# iTimeAfrica_v1_1.net
KiCad netlist of a schematic drawn in Altium Designer
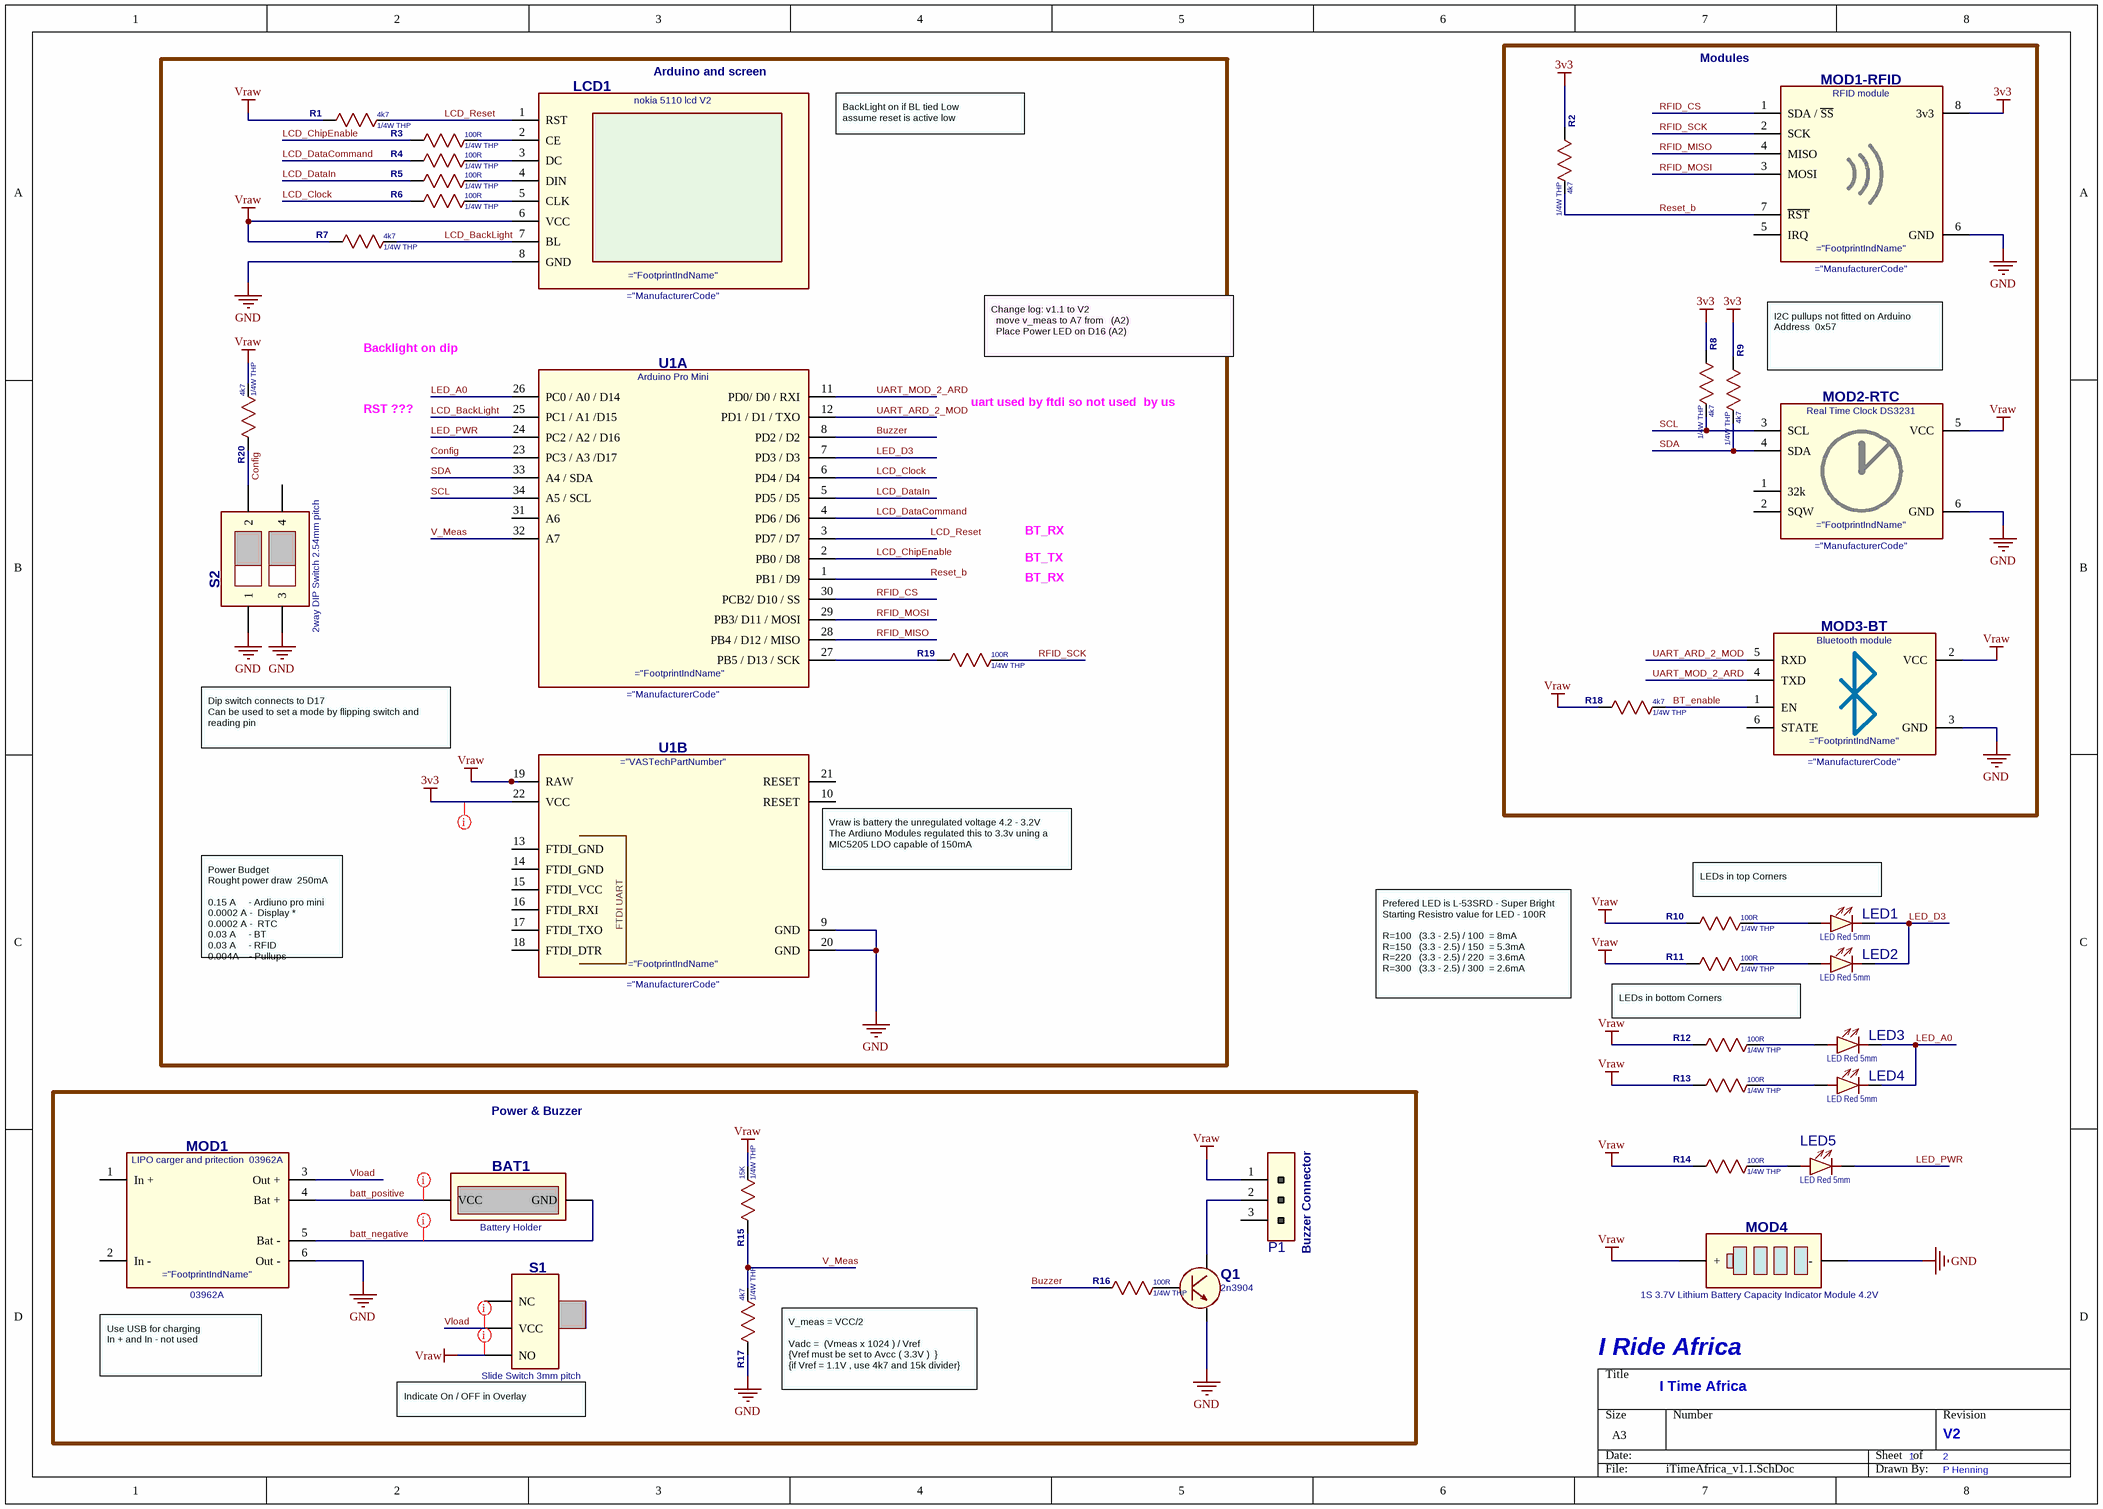
[diagram p0: iTimeAfrica_v1.1.SchDoc]

(export (version "E")
  (design (tool "Eeschema 10.0.6"))
  (components
    (comp (ref "BAT1")
      (value "Battery Holder")
      (footprint "Battery Holder")
      (libsource (lib "Copy of Undero_Symbols_v7") (part "Battery Holder"))
    )
    (comp (ref "LCD1")
      (value "nokia 5110 lcd")
      (footprint "Nokia 5110 GLCD 84x48")
      (description "nokia 5110 lcd V2")
      (fields (field (name "MANUFACTURER") "unknown"))
      (libsource (lib "Copy of Undero_Symbols_v7") (part "nokia 5110 lcd V2"))
    )
    (comp (ref "LED1")
      (value "LED Red 5mm")
      (footprint "LED THL 5x9mm Vert")
      (description "Red LED, 5mm THP")
      (fields
        (field (name "MANUFACTURERPARTNUMBER") "L-53SR")
        (field (name "MANUFACTURER") "kingbright")
        (field (name "ATTRIBUTES") "LED Red 5mm")
      )
      (libsource (lib "Copy of Undero_Symbols_v7") (part "Red LED THP"))
    )
    (comp (ref "LED2")
      (value "LED Red 5mm")
      (footprint "LED THL 5x9mm Vert")
      (description "Red LED, 5mm THP")
      (fields
        (field (name "MANUFACTURERPARTNUMBER") "L-53SR")
        (field (name "MANUFACTURER") "kingbright")
        (field (name "ATTRIBUTES") "LED Red 5mm")
      )
      (libsource (lib "Copy of Undero_Symbols_v7") (part "Red LED THP"))
    )
    (comp (ref "LED3")
      (value "LED Red 5mm")
      (footprint "LED THL 5x9mm Vert")
      (description "Red LED, 5mm THP")
      (fields
        (field (name "MANUFACTURERPARTNUMBER") "L-53SR")
        (field (name "MANUFACTURER") "kingbright")
        (field (name "ATTRIBUTES") "LED Red 5mm")
      )
      (libsource (lib "Copy of Undero_Symbols_v7") (part "Red LED THP"))
    )
    (comp (ref "LED4")
      (value "LED Red 5mm")
      (footprint "LED THL 5x9mm Vert")
      (description "Red LED, 5mm THP")
      (fields
        (field (name "MANUFACTURERPARTNUMBER") "L-53SR")
        (field (name "MANUFACTURER") "kingbright")
        (field (name "ATTRIBUTES") "LED Red 5mm")
      )
      (libsource (lib "Copy of Undero_Symbols_v7") (part "Red LED THP"))
    )
    (comp (ref "LED5")
      (value "LED Red 5mm")
      (footprint "LED THL 5x9mm Vert")
      (description "Red LED, 5mm THP")
      (fields
        (field (name "MANUFACTURERPARTNUMBER") "L-53SR")
        (field (name "MANUFACTURER") "kingbright")
        (field (name "ATTRIBUTES") "LED Red 5mm")
      )
      (libsource (lib "Copy of Undero_Symbols_v7") (part "Red LED THP"))
    )
    (comp (ref "MOD1")
      (value "Real Time Clock DS3231")
      (footprint "Charger/protection")
      (description "LIPO carger and pritection  03962A")
      (fields (field (name "MANUFACTURERPARTNUMBER") "03962A"))
      (libsource (lib "iTimeAfrica_Symbol") (part "Charger / Protection"))
    )
    (comp (ref "MOD1-RFID")
      (value "RFID module")
      (footprint "RFID-RC522")
      (fields (field (name "MANUFACTURERPARTNUMBER") "RFID-RC533"))
      (libsource (lib "Copy of Undero_Symbols_v7") (part "RFID module"))
    )
    (comp (ref "MOD2-RTC")
      (value "Real Time Clock DS3231")
      (footprint "RTC DS3231")
      (libsource (lib "Copy of Undero_Symbols_v7") (part "Real Time Clock DS3231"))
    )
    (comp (ref "MOD3-BT")
      (value "Bluetooth module")
      (footprint "BlueTooth Card")
      (libsource (lib "Copy of Undero_Symbols_v7") (part "Bluetooth module"))
    )
    (comp (ref "MOD4")
      (value "1S 3.7V Lithium Battery Capacity Indicator Module 4.2V")
      (footprint "Battery Indicator")
      (libsource (lib "Copy of Undero_Symbols_v7") (part "Battery Indicator"))
    )
    (comp (ref "P1")
      (value "3 pin Screw Terminal 3.5mm")
      (footprint "3x1 Screw terminal 3.5mm")
      (fields (field (name "MANUFACTURERPARTNUMBER") "1984950") (field (name "MANUFACTURER") "RS"))
      (libsource (lib "Copy of Undero_Symbols_v7") (part "3 pin Screw Terminal 3.5mm"))
    )
    (comp (ref "Q1")
      (value "2n3904")
      (footprint "TO-92")
      (description "NPN Transistor")
      (fields (field (name "MANUFACTURER") "Fairchild") (field (name "ATTRIBUTES") "2n3904"))
      (libsource (lib "Copy of Undero_Symbols_v7") (part "NPN Transistor"))
    )
    (comp (ref "R1")
      (value "4k7")
      (footprint "Res 1/4W THP")
      (description "Resistor")
      (fields (field (name "PACKAGE") "1/4W THP") (field (name "ATTRIBUTES") "4k7"))
      (libsource (lib "Copy of Undero_Symbols_v7") (part "4k7"))
    )
    (comp (ref "R2")
      (value "4k7")
      (footprint "Res 1/4W THP")
      (description "Resistor")
      (fields (field (name "PACKAGE") "1/4W THP") (field (name "ATTRIBUTES") "4k7"))
      (libsource (lib "Copy of Undero_Symbols_v7") (part "4k7"))
    )
    (comp (ref "R3")
      (value "100R")
      (footprint "Res 1/4W THP")
      (description "Resistor")
      (fields (field (name "PACKAGE") "1/4W THP") (field (name "ATTRIBUTES") "100R"))
      (libsource (lib "Copy of Undero_Symbols_v7") (part "100R"))
    )
    (comp (ref "R4")
      (value "100R")
      (footprint "Res 1/4W THP")
      (description "Resistor")
      (fields (field (name "PACKAGE") "1/4W THP") (field (name "ATTRIBUTES") "100R"))
      (libsource (lib "Copy of Undero_Symbols_v7") (part "100R"))
    )
    (comp (ref "R5")
      (value "100R")
      (footprint "Res 1/4W THP")
      (description "Resistor")
      (fields (field (name "PACKAGE") "1/4W THP") (field (name "ATTRIBUTES") "100R"))
      (libsource (lib "Copy of Undero_Symbols_v7") (part "100R"))
    )
    (comp (ref "R6")
      (value "100R")
      (footprint "Res 1/4W THP")
      (description "Resistor")
      (fields (field (name "PACKAGE") "1/4W THP") (field (name "ATTRIBUTES") "100R"))
      (libsource (lib "Copy of Undero_Symbols_v7") (part "100R"))
    )
    (comp (ref "R7")
      (value "4k7")
      (footprint "Res 1/4W THP")
      (description "Resistor")
      (fields (field (name "PACKAGE") "1/4W THP") (field (name "ATTRIBUTES") "4k7"))
      (libsource (lib "Copy of Undero_Symbols_v7") (part "4k7"))
    )
    (comp (ref "R8")
      (value "4k7")
      (footprint "Res 1/4W THP")
      (description "Resistor")
      (fields (field (name "PACKAGE") "1/4W THP") (field (name "ATTRIBUTES") "4k7"))
      (libsource (lib "Copy of Undero_Symbols_v7") (part "4k7"))
    )
    (comp (ref "R9")
      (value "4k7")
      (footprint "Res 1/4W THP")
      (description "Resistor")
      (fields (field (name "PACKAGE") "1/4W THP") (field (name "ATTRIBUTES") "4k7"))
      (libsource (lib "Copy of Undero_Symbols_v7") (part "4k7"))
    )
    (comp (ref "R10")
      (value "100R")
      (footprint "Res 1/4W THP")
      (description "Resistor")
      (fields (field (name "PACKAGE") "1/4W THP") (field (name "ATTRIBUTES") "100R"))
      (libsource (lib "Copy of Undero_Symbols_v7") (part "100R"))
    )
    (comp (ref "R11")
      (value "100R")
      (footprint "Res 1/4W THP")
      (description "Resistor")
      (fields (field (name "PACKAGE") "1/4W THP") (field (name "ATTRIBUTES") "100R"))
      (libsource (lib "Copy of Undero_Symbols_v7") (part "100R"))
    )
    (comp (ref "R12")
      (value "100R")
      (footprint "Res 1/4W THP")
      (description "Resistor")
      (fields (field (name "PACKAGE") "1/4W THP") (field (name "ATTRIBUTES") "100R"))
      (libsource (lib "Copy of Undero_Symbols_v7") (part "100R"))
    )
    (comp (ref "R13")
      (value "100R")
      (footprint "Res 1/4W THP")
      (description "Resistor")
      (fields (field (name "PACKAGE") "1/4W THP") (field (name "ATTRIBUTES") "100R"))
      (libsource (lib "Copy of Undero_Symbols_v7") (part "100R"))
    )
    (comp (ref "R14")
      (value "100R")
      (footprint "Res 1/4W THP")
      (description "Resistor")
      (fields (field (name "PACKAGE") "1/4W THP") (field (name "ATTRIBUTES") "100R"))
      (libsource (lib "Copy of Undero_Symbols_v7") (part "100R"))
    )
    (comp (ref "R15")
      (value "15K")
      (footprint "Res 1/4W THP")
      (description "Resistor")
      (fields (field (name "PACKAGE") "1/4W THP") (field (name "ATTRIBUTES") "15K"))
      (libsource (lib "Copy of Undero_Symbols_v7") (part "15K"))
    )
    (comp (ref "R16")
      (value "100R")
      (footprint "Res 1/4W THP")
      (description "Resistor")
      (fields (field (name "PACKAGE") "1/4W THP") (field (name "ATTRIBUTES") "100R"))
      (libsource (lib "Copy of Undero_Symbols_v7") (part "100R"))
    )
    (comp (ref "R17")
      (value "4k7")
      (footprint "Res 1/4W THP")
      (description "Resistor")
      (fields (field (name "PACKAGE") "1/4W THP") (field (name "ATTRIBUTES") "4k7"))
      (libsource (lib "Copy of Undero_Symbols_v7") (part "4k7"))
    )
    (comp (ref "R18")
      (value "4k7")
      (footprint "Res 1/4W THP")
      (description "Resistor")
      (fields (field (name "PACKAGE") "1/4W THP") (field (name "ATTRIBUTES") "4k7"))
      (libsource (lib "Copy of Undero_Symbols_v7") (part "4k7"))
    )
    (comp (ref "R19")
      (value "100R")
      (footprint "Res 1/4W THP")
      (description "Resistor")
      (fields (field (name "PACKAGE") "1/4W THP") (field (name "ATTRIBUTES") "100R"))
      (libsource (lib "Copy of Undero_Symbols_v7") (part "100R"))
    )
    (comp (ref "R20")
      (value "4k7")
      (footprint "Res 1/4W THP")
      (description "Resistor")
      (fields (field (name "PACKAGE") "1/4W THP") (field (name "ATTRIBUTES") "4k7"))
      (libsource (lib "Copy of Undero_Symbols_v7") (part "4k7"))
    )
    (comp (ref "S1")
      (value "Slide Switch 3mm pitch")
      (footprint "Slide Switch 3mm")
      (fields (field (name "MANUFACTURER") "Arcolectric Corporation"))
      (libsource (lib "Copy of Undero_Symbols_v7") (part "Slide Switch 3mm pitch"))
    )
    (comp (ref "S2")
      (value "2x DIP Switch 2.54mm pitch")
      (footprint "2way DIP switch")
      (description "2way DIP Switch 2.54mm pitch")
      (fields
        (field (name "MANUFACTURER") "Arcolectric Corporation")
        (field (name "MANUFACTURERPARTNUMBER") "KTS02E")
      )
      (libsource (lib "Copy of Undero_Symbols_v7") (part "2way DIP Switch 2.54mm pitch"))
    )
    (comp (ref "U1")
      (value "Arduino Pro Mini")
      (footprint "ARDUINO PRO MINI v2 (NO FTDI)")
      (fields
        (field (name "MANUFACTURER") "SparkFun Electronics")
        (field (name "MANUFACTURERPARTNUMBER") "DEV-11113  (check this)")
      )
      (libsource (lib "Copy of Undero_Symbols_v7") (part "Arduino Pro Mini"))
    )
  )
  (nets
    (net (code "1") (name "/BT_enable") (class "Default")
      (node (ref "MOD3-BT") (pin "1") (pinfunction "EN_1") (pintype "passive"))
      (node (ref "R18") (pin "2") (pinfunction "2_2") (pintype "passive"))
    )
    (net (code "2") (name "/Buzzer") (class "Default")
      (node (ref "R16") (pin "1") (pinfunction "1_1") (pintype "passive"))
      (node (ref "U1") (pin "8") (pinfunction "PD2_/_D2_8") (pintype "passive"))
    )
    (net (code "3") (name "/Config") (class "Default")
      (node (ref "R20") (pin "1") (pinfunction "1_1") (pintype "passive"))
      (node (ref "S2") (pin "2") (pinfunction "2_2") (pintype "passive"))
      (node (ref "U1") (pin "23") (pinfunction "PC3_/_A3_/D17_23") (pintype "passive"))
    )
    (net (code "4") (name "/LCD_BackLight") (class "Default")
      (node (ref "LCD1") (pin "7") (pinfunction "BL_7") (pintype "passive"))
      (node (ref "R7") (pin "2") (pinfunction "2_2") (pintype "passive"))
      (node (ref "U1") (pin "25") (pinfunction "PC1_/_A1_/D15_25") (pintype "passive"))
    )
    (net (code "5") (name "/LCD_ChipEnable") (class "Default")
      (node (ref "R3") (pin "1") (pinfunction "1_1") (pintype "passive"))
      (node (ref "U1") (pin "2") (pinfunction "PB0_/_D8_2") (pintype "passive"))
    )
    (net (code "6") (name "/LCD_Clock") (class "Default")
      (node (ref "R6") (pin "1") (pinfunction "1_1") (pintype "passive"))
      (node (ref "U1") (pin "6") (pinfunction "PD4_/_D4_6") (pintype "passive"))
    )
    (net (code "7") (name "/LCD_DataCommand") (class "Default")
      (node (ref "R4") (pin "1") (pinfunction "1_1") (pintype "passive"))
      (node (ref "U1") (pin "4") (pinfunction "PD6_/_D6_4") (pintype "passive"))
    )
    (net (code "8") (name "/LCD_DataIn") (class "Default")
      (node (ref "R5") (pin "1") (pinfunction "1_1") (pintype "passive"))
      (node (ref "U1") (pin "5") (pinfunction "PD5_/_D5_5") (pintype "passive"))
    )
    (net (code "9") (name "/LCD_Reset") (class "Default")
      (node (ref "LCD1") (pin "1") (pinfunction "RST_1") (pintype "passive"))
      (node (ref "R1") (pin "2") (pinfunction "2_2") (pintype "passive"))
      (node (ref "U1") (pin "3") (pinfunction "PD7_/_D7_3") (pintype "passive"))
    )
    (net (code "10") (name "/LED_A0") (class "Default")
      (node (ref "LED3") (pin "2") (pinfunction "C_2") (pintype "passive"))
      (node (ref "LED4") (pin "2") (pinfunction "C_2") (pintype "passive"))
      (node (ref "U1") (pin "26") (pinfunction "PC0_/_A0_/_D14_26") (pintype "passive"))
    )
    (net (code "11") (name "/LED_D3") (class "Default")
      (node (ref "LED1") (pin "2") (pinfunction "C_2") (pintype "passive"))
      (node (ref "LED2") (pin "2") (pinfunction "C_2") (pintype "passive"))
      (node (ref "U1") (pin "7") (pinfunction "PD3_/_D3_7") (pintype "passive"))
    )
    (net (code "12") (name "/LED_PWR") (class "Default")
      (node (ref "LED5") (pin "2") (pinfunction "C_2") (pintype "passive"))
      (node (ref "U1") (pin "24") (pinfunction "PC2_/_A2_/_D16_24") (pintype "passive"))
    )
    (net (code "13") (name "/RFID_CS") (class "Default")
      (node (ref "MOD1-RFID") (pin "1") (pinfunction "SDA_/_~{SS}_1") (pintype "passive"))
      (node (ref "U1") (pin "30") (pinfunction "PCB2/_D10_/_SS_30") (pintype "passive"))
    )
    (net (code "14") (name "/RFID_MISO") (class "Default")
      (node (ref "MOD1-RFID") (pin "4") (pinfunction "MISO_4") (pintype "passive"))
      (node (ref "U1") (pin "28") (pinfunction "PB4_/_D12_/_MISO_28") (pintype "passive"))
    )
    (net (code "15") (name "/RFID_MOSI") (class "Default")
      (node (ref "MOD1-RFID") (pin "3") (pinfunction "MOSI_3") (pintype "passive"))
      (node (ref "U1") (pin "29") (pinfunction "PB3/_D11_/_MOSI_29") (pintype "passive"))
    )
    (net (code "16") (name "/RFID_SCK") (class "Default")
      (node (ref "MOD1-RFID") (pin "2") (pinfunction "SCK_2") (pintype "passive"))
      (node (ref "R19") (pin "2") (pinfunction "2_2") (pintype "passive"))
    )
    (net (code "17") (name "/Reset_b") (class "Default")
      (node (ref "MOD1-RFID") (pin "7") (pinfunction "RST_7") (pintype "passive"))
      (node (ref "R2") (pin "2") (pinfunction "2_2") (pintype "passive"))
      (node (ref "U1") (pin "1") (pinfunction "PB1_/_D9_1") (pintype "passive"))
    )
    (net (code "18") (name "/SCL") (class "Default")
      (node (ref "MOD2-RTC") (pin "3") (pinfunction "SCL_3") (pintype "passive"))
      (node (ref "R8") (pin "2") (pinfunction "2_2") (pintype "passive"))
      (node (ref "U1") (pin "34") (pinfunction "A5_/_SCL_34") (pintype "passive"))
    )
    (net (code "19") (name "/SDA") (class "Default")
      (node (ref "MOD2-RTC") (pin "4") (pinfunction "SDA_4") (pintype "passive"))
      (node (ref "R9") (pin "2") (pinfunction "2_2") (pintype "passive"))
      (node (ref "U1") (pin "33") (pinfunction "A4_/_SDA_33") (pintype "passive"))
    )
    (net (code "20") (name "/UART_ARD_2_MOD") (class "Default")
      (node (ref "MOD3-BT") (pin "5") (pinfunction "RXD_5") (pintype "passive"))
      (node (ref "U1") (pin "12") (pinfunction "PD1_/_D1_/_TXO_12") (pintype "passive"))
    )
    (net (code "21") (name "/UART_MOD_2_ARD") (class "Default")
      (node (ref "MOD3-BT") (pin "4") (pinfunction "TXD_4") (pintype "passive"))
      (node (ref "U1") (pin "11") (pinfunction "PD0/_D0_/_RXI_11") (pintype "passive"))
    )
    (net (code "22") (name "/V_Meas") (class "Default")
      (node (ref "R15") (pin "1") (pinfunction "1_1") (pintype "passive"))
      (node (ref "R17") (pin "2") (pinfunction "2_2") (pintype "passive"))
      (node (ref "U1") (pin "32") (pinfunction "A7_32") (pintype "passive"))
    )
    (net (code "23") (name "/Vload") (class "Default")
      (node (ref "MOD1") (pin "3") (pinfunction "Out_+_3") (pintype "passive"))
      (node (ref "S1") (pin "2") (pinfunction "VCC_2") (pintype "passive"))
    )
    (net (code "24") (name "/batt_negative") (class "Default")
      (node (ref "BAT1") (pin "2") (pinfunction "GND_2") (pintype "passive"))
      (node (ref "MOD1") (pin "5") (pinfunction "Bat_-_5") (pintype "passive"))
    )
    (net (code "25") (name "/batt_positive") (class "Default")
      (node (ref "BAT1") (pin "1") (pinfunction "VCC_1") (pintype "passive"))
      (node (ref "MOD1") (pin "4") (pinfunction "Bat_+_4") (pintype "passive"))
    )
    (net (code "26") (name "3v3") (class "Default")
      (node (ref "MOD1-RFID") (pin "8") (pinfunction "3v3_8") (pintype "passive"))
      (node (ref "R2") (pin "1") (pinfunction "1_1") (pintype "passive"))
      (node (ref "R8") (pin "1") (pinfunction "1_1") (pintype "passive"))
      (node (ref "R9") (pin "1") (pinfunction "1_1") (pintype "passive"))
      (node (ref "U1") (pin "22") (pinfunction "VCC_22") (pintype "passive"))
    )
    (net (code "27") (name "GND") (class "Default")
      (node (ref "LCD1") (pin "8") (pinfunction "GND_8") (pintype "passive"))
      (node (ref "MOD1") (pin "6") (pinfunction "Out_-_6") (pintype "passive"))
      (node (ref "MOD1-RFID") (pin "6") (pinfunction "GND_6") (pintype "passive"))
      (node (ref "MOD2-RTC") (pin "6") (pinfunction "GND_6") (pintype "passive"))
      (node (ref "MOD3-BT") (pin "3") (pinfunction "GND_3") (pintype "passive"))
      (node (ref "MOD4") (pin "2") (pinfunction "-_2") (pintype "passive"))
      (node (ref "Q1") (pin "3") (pinfunction "E_3") (pintype "passive"))
      (node (ref "R17") (pin "1") (pinfunction "1_1") (pintype "passive"))
      (node (ref "S2") (pin "1") (pinfunction "1_1") (pintype "passive"))
      (node (ref "S2") (pin "3") (pinfunction "3_3") (pintype "passive"))
      (node (ref "U1") (pin "20") (pinfunction "GND_20") (pintype "passive"))
      (node (ref "U1") (pin "9") (pinfunction "GND_9") (pintype "passive"))
    )
    (net (code "28") (name "Net-(LCD1-CE)") (class "Default")
      (node (ref "LCD1") (pin "2") (pinfunction "CE_2") (pintype "passive"))
      (node (ref "R3") (pin "2") (pinfunction "2_2") (pintype "passive"))
    )
    (net (code "29") (name "Net-(LCD1-CLK)") (class "Default")
      (node (ref "LCD1") (pin "5") (pinfunction "CLK_5") (pintype "passive"))
      (node (ref "R6") (pin "2") (pinfunction "2_2") (pintype "passive"))
    )
    (net (code "30") (name "Net-(LCD1-DC)") (class "Default")
      (node (ref "LCD1") (pin "3") (pinfunction "DC_3") (pintype "passive"))
      (node (ref "R4") (pin "2") (pinfunction "2_2") (pintype "passive"))
    )
    (net (code "31") (name "Net-(LCD1-DIN)") (class "Default")
      (node (ref "LCD1") (pin "4") (pinfunction "DIN_4") (pintype "passive"))
      (node (ref "R5") (pin "2") (pinfunction "2_2") (pintype "passive"))
    )
    (net (code "32") (name "Net-(LED1-A)") (class "Default")
      (node (ref "LED1") (pin "1") (pinfunction "A_1") (pintype "passive"))
      (node (ref "R10") (pin "2") (pinfunction "2_2") (pintype "passive"))
    )
    (net (code "33") (name "Net-(LED2-A)") (class "Default")
      (node (ref "LED2") (pin "1") (pinfunction "A_1") (pintype "passive"))
      (node (ref "R11") (pin "2") (pinfunction "2_2") (pintype "passive"))
    )
    (net (code "34") (name "Net-(LED3-A)") (class "Default")
      (node (ref "LED3") (pin "1") (pinfunction "A_1") (pintype "passive"))
      (node (ref "R12") (pin "2") (pinfunction "2_2") (pintype "passive"))
    )
    (net (code "35") (name "Net-(LED4-A)") (class "Default")
      (node (ref "LED4") (pin "1") (pinfunction "A_1") (pintype "passive"))
      (node (ref "R13") (pin "2") (pinfunction "2_2") (pintype "passive"))
    )
    (net (code "36") (name "Net-(LED5-A)") (class "Default")
      (node (ref "LED5") (pin "1") (pinfunction "A_1") (pintype "passive"))
      (node (ref "R14") (pin "2") (pinfunction "2_2") (pintype "passive"))
    )
    (net (code "37") (name "Net-(Q1-B)") (class "Default")
      (node (ref "Q1") (pin "2") (pinfunction "B_2") (pintype "passive"))
      (node (ref "R16") (pin "2") (pinfunction "2_2") (pintype "passive"))
    )
    (net (code "38") (name "Net-(Q1-C)") (class "Default")
      (node (ref "P1") (pin "2") (pinfunction "2_2") (pintype "passive"))
      (node (ref "Q1") (pin "1") (pinfunction "C_1") (pintype "passive"))
    )
    (net (code "39") (name "Net-(U1A-PB5_{slash}_D13_{slash}_SCK)") (class "Default")
      (node (ref "R19") (pin "1") (pinfunction "1_1") (pintype "passive"))
      (node (ref "U1") (pin "27") (pinfunction "PB5_/_D13_/_SCK_27") (pintype "passive"))
    )
    (net (code "40") (name "Vraw") (class "Default")
      (node (ref "LCD1") (pin "6") (pinfunction "VCC_6") (pintype "passive"))
      (node (ref "MOD2-RTC") (pin "5") (pinfunction "VCC_5") (pintype "passive"))
      (node (ref "MOD3-BT") (pin "2") (pinfunction "VCC_2") (pintype "passive"))
      (node (ref "MOD4") (pin "1") (pinfunction "+_1") (pintype "passive"))
      (node (ref "P1") (pin "1") (pinfunction "1_1") (pintype "passive"))
      (node (ref "R1") (pin "1") (pinfunction "1_1") (pintype "passive"))
      (node (ref "R10") (pin "1") (pinfunction "1_1") (pintype "passive"))
      (node (ref "R11") (pin "1") (pinfunction "1_1") (pintype "passive"))
      (node (ref "R12") (pin "1") (pinfunction "1_1") (pintype "passive"))
      (node (ref "R13") (pin "1") (pinfunction "1_1") (pintype "passive"))
      (node (ref "R14") (pin "1") (pinfunction "1_1") (pintype "passive"))
      (node (ref "R15") (pin "2") (pinfunction "2_2") (pintype "passive"))
      (node (ref "R18") (pin "1") (pinfunction "1_1") (pintype "passive"))
      (node (ref "R20") (pin "2") (pinfunction "2_2") (pintype "passive"))
      (node (ref "R7") (pin "1") (pinfunction "1_1") (pintype "passive"))
      (node (ref "S1") (pin "3") (pinfunction "NO_3") (pintype "passive"))
      (node (ref "U1") (pin "19") (pinfunction "RAW_19") (pintype "passive"))
    )
    (net (code "41") (name "unconnected-(MOD1-In_+-Pad1)") (class "Default")
      (node (ref "MOD1") (pin "1") (pinfunction "In_+_1") (pintype "passive"))
    )
    (net (code "42") (name "unconnected-(MOD1-In_--Pad2)") (class "Default")
      (node (ref "MOD1") (pin "2") (pinfunction "In_-_2") (pintype "passive"))
    )
    (net (code "43") (name "unconnected-(MOD1-RFID-IRQ-Pad5)") (class "Default")
      (node (ref "MOD1-RFID") (pin "5") (pinfunction "IRQ_5") (pintype "passive"))
    )
    (net (code "44") (name "unconnected-(MOD2-RTC-32k-Pad1)") (class "Default")
      (node (ref "MOD2-RTC") (pin "1") (pinfunction "32k_1") (pintype "passive"))
    )
    (net (code "45") (name "unconnected-(MOD2-RTC-SQW-Pad2)") (class "Default")
      (node (ref "MOD2-RTC") (pin "2") (pinfunction "SQW_2") (pintype "passive"))
    )
    (net (code "46") (name "unconnected-(MOD3-BT-STATE-Pad6)") (class "Default")
      (node (ref "MOD3-BT") (pin "6") (pinfunction "STATE_6") (pintype "passive"))
    )
    (net (code "47") (name "unconnected-(P1-Pad3)") (class "Default")
      (node (ref "P1") (pin "3") (pinfunction "3_3") (pintype "passive"))
    )
    (net (code "48") (name "unconnected-(S1-NC-Pad1)") (class "Default")
      (node (ref "S1") (pin "1") (pinfunction "NC_1") (pintype "passive"))
    )
    (net (code "49") (name "unconnected-(S2-Pad4)") (class "Default")
      (node (ref "S2") (pin "4") (pinfunction "4_4") (pintype "passive"))
    )
    (net (code "50") (name "unconnected-(U1A-A6-Pad31)") (class "Default")
      (node (ref "U1") (pin "31") (pinfunction "A6_31") (pintype "passive"))
    )
    (net (code "51") (name "unconnected-(U1B-FTDI_DTR-Pad18)") (class "Default")
      (node (ref "U1") (pin "18") (pinfunction "FTDI_DTR_18") (pintype "passive"))
    )
    (net (code "52") (name "unconnected-(U1B-FTDI_GND-Pad13)") (class "Default")
      (node (ref "U1") (pin "13") (pinfunction "FTDI_GND_13") (pintype "passive"))
    )
    (net (code "53") (name "unconnected-(U1B-FTDI_GND-Pad14)") (class "Default")
      (node (ref "U1") (pin "14") (pinfunction "FTDI_GND_14") (pintype "passive"))
    )
    (net (code "54") (name "unconnected-(U1B-FTDI_RXI-Pad16)") (class "Default")
      (node (ref "U1") (pin "16") (pinfunction "FTDI_RXI_16") (pintype "passive"))
    )
    (net (code "55") (name "unconnected-(U1B-FTDI_TXO-Pad17)") (class "Default")
      (node (ref "U1") (pin "17") (pinfunction "FTDI_TXO_17") (pintype "passive"))
    )
    (net (code "56") (name "unconnected-(U1B-FTDI_VCC-Pad15)") (class "Default")
      (node (ref "U1") (pin "15") (pinfunction "FTDI_VCC_15") (pintype "passive"))
    )
    (net (code "57") (name "unconnected-(U1B-RESET-Pad10)") (class "Default")
      (node (ref "U1") (pin "10") (pinfunction "RESET_10") (pintype "passive"))
    )
    (net (code "58") (name "unconnected-(U1B-RESET-Pad21)") (class "Default")
      (node (ref "U1") (pin "21") (pinfunction "RESET_21") (pintype "passive"))
    )
  )
)
